# activity_monitor_v0.net
KiCad netlist of a schematic drawn in EAGLE
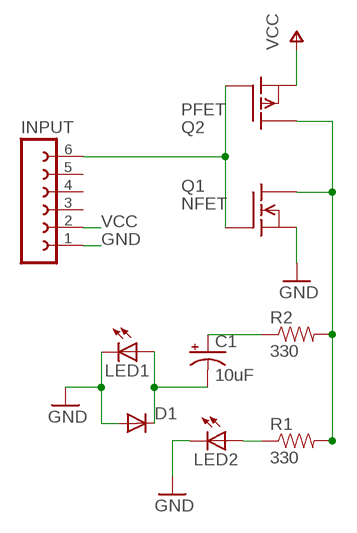
[diagram p0: schematic, sheet 1]

(export (version "E")
  (design (tool "Eeschema 10.0.6"))
  (components
    (comp (ref "C1")
      (value "10uF")
      (footprint "eagle-import:CPOL-RADIAL-10UF-25V")
      (libsource (lib "eagle-import") (part "CAP_POLPTH2"))
    )
    (comp (ref "D1")
      (value "1N4004")
      (footprint "eagle-import:DO41-10")
      (libsource (lib "eagle-import") (part "1N4004"))
    )
    (comp (ref "INPUT")
      (value "FE06-1")
      (footprint "eagle-import:FE06")
      (libsource (lib "eagle-import") (part "FE06-1"))
    )
    (comp (ref "LED1")
      (value "LED5MM")
      (footprint "eagle-import:LED5MM")
      (libsource (lib "eagle-import") (part "LED5MM"))
    )
    (comp (ref "LED2")
      (value "LED5MM")
      (footprint "eagle-import:LED5MM")
      (libsource (lib "eagle-import") (part "LED5MM"))
    )
    (comp (ref "Q1")
      (value "NFET")
      (footprint "eagle-import:TO220")
      (libsource (lib "eagle-import") (part "BUZ10"))
    )
    (comp (ref "Q2")
      (value "PFET")
      (footprint "eagle-import:TO220")
      (libsource (lib "eagle-import") (part "BUZ171"))
    )
    (comp (ref "R1")
      (value "330")
      (footprint "eagle-import:AXIAL-0.3")
      (libsource (lib "eagle-import") (part "RESISTORAXIAL-0.3"))
    )
    (comp (ref "R2")
      (value "330")
      (footprint "eagle-import:AXIAL-0.3")
      (libsource (lib "eagle-import") (part "RESISTORAXIAL-0.3"))
    )
  )
  (nets
    (net (code "1") (name "GND") (class "Default")
      (node (ref "D1") (pin "A") (pinfunction "A_A") (pintype "passive"))
      (node (ref "INPUT") (pin "1") (pinfunction "1_1") (pintype "passive"))
      (node (ref "LED1") (pin "K") (pinfunction "C_K") (pintype "passive"))
      (node (ref "LED2") (pin "K") (pinfunction "C_K") (pintype "passive"))
      (node (ref "Q1") (pin "3") (pinfunction "S_3") (pintype "passive"))
    )
    (net (code "2") (name "Net-(C1-+)") (class "Default")
      (node (ref "C1") (pin "1") (pinfunction "+_1") (pintype "passive"))
      (node (ref "R2") (pin "P$1") (pinfunction "1_P$1") (pintype "passive"))
    )
    (net (code "3") (name "Net-(C1--)") (class "Default")
      (node (ref "C1") (pin "2") (pinfunction "-_2") (pintype "passive"))
      (node (ref "D1") (pin "C") (pinfunction "C_C") (pintype "passive"))
      (node (ref "LED1") (pin "A") (pinfunction "A_A") (pintype "passive"))
    )
    (net (code "4") (name "Net-(Q1-D)") (class "Default")
      (node (ref "Q1") (pin "2") (pinfunction "D_2") (pintype "passive"))
      (node (ref "Q2") (pin "2") (pinfunction "D_2") (pintype "passive"))
      (node (ref "R1") (pin "P$2") (pinfunction "2_P$2") (pintype "passive"))
      (node (ref "R2") (pin "P$2") (pinfunction "2_P$2") (pintype "passive"))
    )
    (net (code "5") (name "Net-(Q1-G)") (class "Default")
      (node (ref "INPUT") (pin "6") (pinfunction "6_6") (pintype "passive"))
      (node (ref "Q1") (pin "1") (pinfunction "G_1") (pintype "passive"))
      (node (ref "Q2") (pin "1") (pinfunction "G_1") (pintype "passive"))
    )
    (net (code "6") (name "Net-(R1-1)") (class "Default")
      (node (ref "LED2") (pin "A") (pinfunction "A_A") (pintype "passive"))
      (node (ref "R1") (pin "P$1") (pinfunction "1_P$1") (pintype "passive"))
    )
    (net (code "7") (name "VCC") (class "Default")
      (node (ref "INPUT") (pin "2") (pinfunction "2_2") (pintype "passive"))
      (node (ref "Q2") (pin "3") (pinfunction "S_3") (pintype "passive"))
    )
    (net (code "8") (name "unconnected-(INPUT-Pad3)") (class "Default")
      (node (ref "INPUT") (pin "3") (pinfunction "3_3") (pintype "passive"))
    )
    (net (code "9") (name "unconnected-(INPUT-Pad4)") (class "Default")
      (node (ref "INPUT") (pin "4") (pinfunction "4_4") (pintype "passive"))
    )
    (net (code "10") (name "unconnected-(INPUT-Pad5)") (class "Default")
      (node (ref "INPUT") (pin "5") (pinfunction "5_5") (pintype "passive"))
    )
  )
)
